# S7CAS-PLEIADES-CARTE-MERE_P02_FPGA_B4B5.net
KiCad netlist of a schematic drawn in Altium Designer
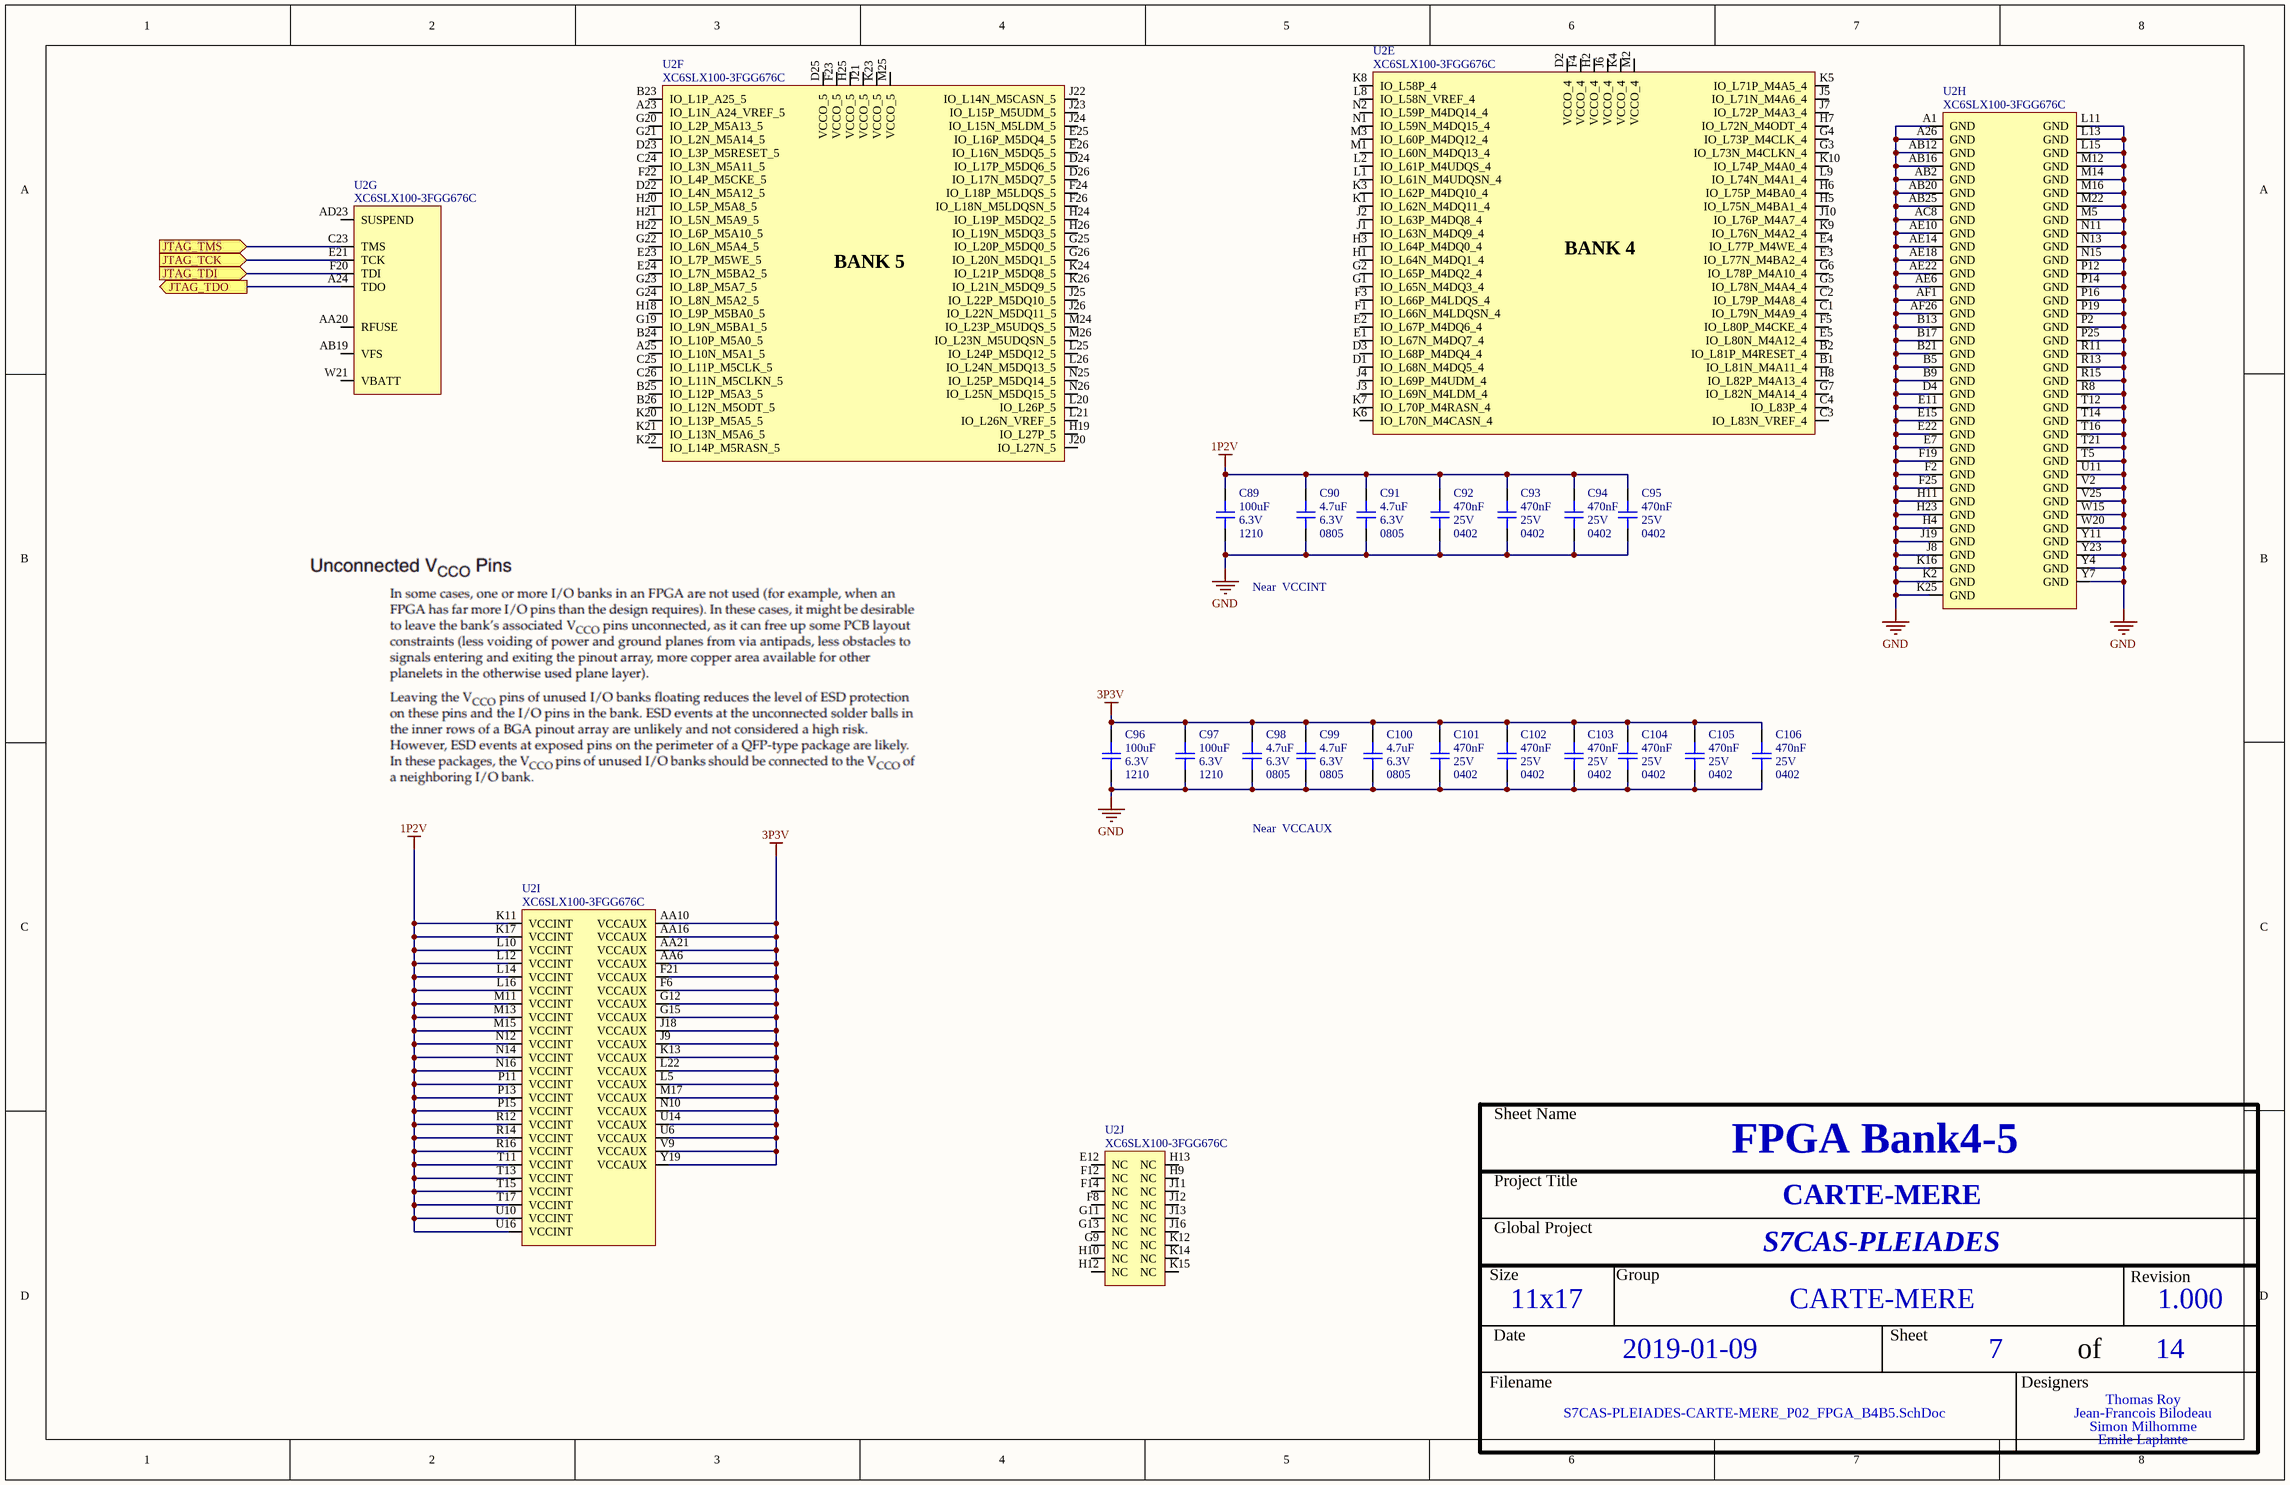
[diagram p0: S7CAS-PLEIADES-CARTE-MERE_P02_FPGA_B4B5.SchDoc]

(export (version "E")
  (design (tool "Eeschema 10.0.6"))
  (components
    (comp (ref "C89")
      (value "100uF")
      (footprint "CAP_1210")
      (description "CAP - 1210")
      (fields
        (field (name "VOLTAGE") "6.3V")
        (field (name "PACKAGE") "1210")
        (field (name "CREATEDBY") "Jonathan Bouchard")
      )
      (libsource (lib "S7CAS_Lib2019_REV1_00") (part "CAP - 1210"))
    )
    (comp (ref "C90")
      (value "4.7uF")
      (footprint "CAP_0805")
      (description "CAP - 0805")
      (fields
        (field (name "VOLTAGE") "6.3V")
        (field (name "PACKAGE") "0805")
        (field (name "CREATEDBY") "Jonathan Bouchard")
      )
      (libsource (lib "S7CAS_Lib2019_REV1_00") (part "CAP - 0805"))
    )
    (comp (ref "C91")
      (value "4.7uF")
      (footprint "CAP_0805")
      (description "CAP - 0805")
      (fields
        (field (name "VOLTAGE") "6.3V")
        (field (name "PACKAGE") "0805")
        (field (name "CREATEDBY") "Jonathan Bouchard")
      )
      (libsource (lib "S7CAS_Lib2019_REV1_00") (part "CAP - 0805"))
    )
    (comp (ref "C92")
      (value "470nF")
      (footprint "CAP_0402")
      (description "CAP - 0402")
      (fields
        (field (name "VOLTAGE") "25V")
        (field (name "PACKAGE") "0402")
        (field (name "CREATEDBY") "Jonathan Bouchard")
      )
      (libsource (lib "S7CAS_Lib2019_REV1_00") (part "CAP - 0402"))
    )
    (comp (ref "C93")
      (value "470nF")
      (footprint "CAP_0402")
      (description "CAP - 0402")
      (fields
        (field (name "VOLTAGE") "25V")
        (field (name "PACKAGE") "0402")
        (field (name "CREATEDBY") "Jonathan Bouchard")
      )
      (libsource (lib "S7CAS_Lib2019_REV1_00") (part "CAP - 0402"))
    )
    (comp (ref "C94")
      (value "470nF")
      (footprint "CAP_0402")
      (description "CAP - 0402")
      (fields
        (field (name "VOLTAGE") "25V")
        (field (name "PACKAGE") "0402")
        (field (name "CREATEDBY") "Jonathan Bouchard")
      )
      (libsource (lib "S7CAS_Lib2019_REV1_00") (part "CAP - 0402"))
    )
    (comp (ref "C95")
      (value "470nF")
      (footprint "CAP_0402")
      (description "CAP - 0402")
      (fields
        (field (name "VOLTAGE") "25V")
        (field (name "PACKAGE") "0402")
        (field (name "CREATEDBY") "Jonathan Bouchard")
      )
      (libsource (lib "S7CAS_Lib2019_REV1_00") (part "CAP - 0402"))
    )
    (comp (ref "C96")
      (value "100uF")
      (footprint "CAP_1210")
      (description "CAP - 1210")
      (fields
        (field (name "VOLTAGE") "6.3V")
        (field (name "PACKAGE") "1210")
        (field (name "CREATEDBY") "Jonathan Bouchard")
      )
      (libsource (lib "S7CAS_Lib2019_REV1_00") (part "CAP - 1210"))
    )
    (comp (ref "C97")
      (value "100uF")
      (footprint "CAP_1210")
      (description "CAP - 1210")
      (fields
        (field (name "VOLTAGE") "6.3V")
        (field (name "PACKAGE") "1210")
        (field (name "CREATEDBY") "Jonathan Bouchard")
      )
      (libsource (lib "S7CAS_Lib2019_REV1_00") (part "CAP - 1210"))
    )
    (comp (ref "C98")
      (value "4.7uF")
      (footprint "CAP_0805")
      (description "CAP - 0805")
      (fields
        (field (name "VOLTAGE") "6.3V")
        (field (name "PACKAGE") "0805")
        (field (name "CREATEDBY") "Jonathan Bouchard")
      )
      (libsource (lib "S7CAS_Lib2019_REV1_00") (part "CAP - 0805"))
    )
    (comp (ref "C99")
      (value "4.7uF")
      (footprint "CAP_0805")
      (description "CAP - 0805")
      (fields
        (field (name "VOLTAGE") "6.3V")
        (field (name "PACKAGE") "0805")
        (field (name "CREATEDBY") "Jonathan Bouchard")
      )
      (libsource (lib "S7CAS_Lib2019_REV1_00") (part "CAP - 0805"))
    )
    (comp (ref "C100")
      (value "4.7uF")
      (footprint "CAP_0805")
      (description "CAP - 0805")
      (fields
        (field (name "VOLTAGE") "6.3V")
        (field (name "PACKAGE") "0805")
        (field (name "CREATEDBY") "Jonathan Bouchard")
      )
      (libsource (lib "S7CAS_Lib2019_REV1_00") (part "CAP - 0805"))
    )
    (comp (ref "C101")
      (value "470nF")
      (footprint "CAP_0402")
      (description "CAP - 0402")
      (fields
        (field (name "VOLTAGE") "25V")
        (field (name "PACKAGE") "0402")
        (field (name "CREATEDBY") "Jonathan Bouchard")
      )
      (libsource (lib "S7CAS_Lib2019_REV1_00") (part "CAP - 0402"))
    )
    (comp (ref "C102")
      (value "470nF")
      (footprint "CAP_0402")
      (description "CAP - 0402")
      (fields
        (field (name "VOLTAGE") "25V")
        (field (name "PACKAGE") "0402")
        (field (name "CREATEDBY") "Jonathan Bouchard")
      )
      (libsource (lib "S7CAS_Lib2019_REV1_00") (part "CAP - 0402"))
    )
    (comp (ref "C103")
      (value "470nF")
      (footprint "CAP_0402")
      (description "CAP - 0402")
      (fields
        (field (name "VOLTAGE") "25V")
        (field (name "PACKAGE") "0402")
        (field (name "CREATEDBY") "Jonathan Bouchard")
      )
      (libsource (lib "S7CAS_Lib2019_REV1_00") (part "CAP - 0402"))
    )
    (comp (ref "C104")
      (value "470nF")
      (footprint "CAP_0402")
      (description "CAP - 0402")
      (fields
        (field (name "VOLTAGE") "25V")
        (field (name "PACKAGE") "0402")
        (field (name "CREATEDBY") "Jonathan Bouchard")
      )
      (libsource (lib "S7CAS_Lib2019_REV1_00") (part "CAP - 0402"))
    )
    (comp (ref "C105")
      (value "470nF")
      (footprint "CAP_0402")
      (description "CAP - 0402")
      (fields
        (field (name "VOLTAGE") "25V")
        (field (name "PACKAGE") "0402")
        (field (name "CREATEDBY") "Jonathan Bouchard")
      )
      (libsource (lib "S7CAS_Lib2019_REV1_00") (part "CAP - 0402"))
    )
    (comp (ref "C106")
      (value "470nF")
      (footprint "CAP_0402")
      (description "CAP - 0402")
      (fields
        (field (name "VOLTAGE") "25V")
        (field (name "PACKAGE") "0402")
        (field (name "CREATEDBY") "Jonathan Bouchard")
      )
      (libsource (lib "S7CAS_Lib2019_REV1_00") (part "CAP - 0402"))
    )
    (comp (ref "U2")
      (value "XC6SLX100-3FGG676C")
      (footprint "FPGA_XILINX_FGG676")
      (description "FPGA - XILINX SPARTAN 6 480 I/O - BGA-676")
      (fields
        (field (name "VOLTAGE") "1.14 V ~ 1.26 V")
        (field (name "MFG") "Xilinx")
        (field (name "CREATEDBY") "Jonathan Bouchard")
      )
      (libsource (lib "S7CAS_Lib2019_REV1_00") (part "FPGA_XC6SLX100-3FGG676C"))
    )
  )
  (nets
    (net (code "1") (name "/JTAG_TCK") (class "Default")
      (node (ref "U2") (pin "E21") (pinfunction "TCK_E21") (pintype "passive"))
    )
    (net (code "2") (name "/JTAG_TDI") (class "Default")
      (node (ref "U2") (pin "F20") (pinfunction "TDI_F20") (pintype "passive"))
    )
    (net (code "3") (name "/JTAG_TDO") (class "Default")
      (node (ref "U2") (pin "A24") (pinfunction "TDO_A24") (pintype "passive"))
    )
    (net (code "4") (name "/JTAG_TMS") (class "Default")
      (node (ref "U2") (pin "C23") (pinfunction "TMS_C23") (pintype "passive"))
    )
    (net (code "5") (name "1P2V") (class "Default")
      (node (ref "C89") (pin "2") (pinfunction "2_2") (pintype "passive"))
      (node (ref "C90") (pin "2") (pinfunction "2_2") (pintype "passive"))
      (node (ref "C91") (pin "2") (pinfunction "2_2") (pintype "passive"))
      (node (ref "C92") (pin "2") (pinfunction "2_2") (pintype "passive"))
      (node (ref "C93") (pin "2") (pinfunction "2_2") (pintype "passive"))
      (node (ref "C94") (pin "2") (pinfunction "2_2") (pintype "passive"))
      (node (ref "C95") (pin "2") (pinfunction "2_2") (pintype "passive"))
      (node (ref "U2") (pin "K11") (pinfunction "VCCINT_K11") (pintype "passive"))
      (node (ref "U2") (pin "K17") (pinfunction "VCCINT_K17") (pintype "passive"))
      (node (ref "U2") (pin "L10") (pinfunction "VCCINT_L10") (pintype "passive"))
      (node (ref "U2") (pin "L12") (pinfunction "VCCINT_L12") (pintype "passive"))
      (node (ref "U2") (pin "L14") (pinfunction "VCCINT_L14") (pintype "passive"))
      (node (ref "U2") (pin "L16") (pinfunction "VCCINT_L16") (pintype "passive"))
      (node (ref "U2") (pin "M11") (pinfunction "VCCINT_M11") (pintype "passive"))
      (node (ref "U2") (pin "M13") (pinfunction "VCCINT_M13") (pintype "passive"))
      (node (ref "U2") (pin "M15") (pinfunction "VCCINT_M15") (pintype "passive"))
      (node (ref "U2") (pin "N12") (pinfunction "VCCINT_N12") (pintype "passive"))
      (node (ref "U2") (pin "N14") (pinfunction "VCCINT_N14") (pintype "passive"))
      (node (ref "U2") (pin "N16") (pinfunction "VCCINT_N16") (pintype "passive"))
      (node (ref "U2") (pin "P11") (pinfunction "VCCINT_P11") (pintype "passive"))
      (node (ref "U2") (pin "P13") (pinfunction "VCCINT_P13") (pintype "passive"))
      (node (ref "U2") (pin "P15") (pinfunction "VCCINT_P15") (pintype "passive"))
      (node (ref "U2") (pin "R12") (pinfunction "VCCINT_R12") (pintype "passive"))
      (node (ref "U2") (pin "R14") (pinfunction "VCCINT_R14") (pintype "passive"))
      (node (ref "U2") (pin "R16") (pinfunction "VCCINT_R16") (pintype "passive"))
      (node (ref "U2") (pin "T11") (pinfunction "VCCINT_T11") (pintype "passive"))
      (node (ref "U2") (pin "T13") (pinfunction "VCCINT_T13") (pintype "passive"))
      (node (ref "U2") (pin "T15") (pinfunction "VCCINT_T15") (pintype "passive"))
      (node (ref "U2") (pin "T17") (pinfunction "VCCINT_T17") (pintype "passive"))
      (node (ref "U2") (pin "U10") (pinfunction "VCCINT_U10") (pintype "passive"))
      (node (ref "U2") (pin "U16") (pinfunction "VCCINT_U16") (pintype "passive"))
    )
    (net (code "6") (name "3P3V") (class "Default")
      (node (ref "C100") (pin "2") (pinfunction "2_2") (pintype "passive"))
      (node (ref "C101") (pin "2") (pinfunction "2_2") (pintype "passive"))
      (node (ref "C102") (pin "2") (pinfunction "2_2") (pintype "passive"))
      (node (ref "C103") (pin "2") (pinfunction "2_2") (pintype "passive"))
      (node (ref "C104") (pin "2") (pinfunction "2_2") (pintype "passive"))
      (node (ref "C105") (pin "2") (pinfunction "2_2") (pintype "passive"))
      (node (ref "C106") (pin "2") (pinfunction "2_2") (pintype "passive"))
      (node (ref "C96") (pin "2") (pinfunction "2_2") (pintype "passive"))
      (node (ref "C97") (pin "2") (pinfunction "2_2") (pintype "passive"))
      (node (ref "C98") (pin "2") (pinfunction "2_2") (pintype "passive"))
      (node (ref "C99") (pin "2") (pinfunction "2_2") (pintype "passive"))
      (node (ref "U2") (pin "AA10") (pinfunction "VCCAUX_AA10") (pintype "passive"))
      (node (ref "U2") (pin "AA16") (pinfunction "VCCAUX_AA16") (pintype "passive"))
      (node (ref "U2") (pin "AA21") (pinfunction "VCCAUX_AA21") (pintype "passive"))
      (node (ref "U2") (pin "AA6") (pinfunction "VCCAUX_AA6") (pintype "passive"))
      (node (ref "U2") (pin "F21") (pinfunction "VCCAUX_F21") (pintype "passive"))
      (node (ref "U2") (pin "F6") (pinfunction "VCCAUX_F6") (pintype "passive"))
      (node (ref "U2") (pin "G12") (pinfunction "VCCAUX_G12") (pintype "passive"))
      (node (ref "U2") (pin "G15") (pinfunction "VCCAUX_G15") (pintype "passive"))
      (node (ref "U2") (pin "J18") (pinfunction "VCCAUX_J18") (pintype "passive"))
      (node (ref "U2") (pin "J9") (pinfunction "VCCAUX_J9") (pintype "passive"))
      (node (ref "U2") (pin "K13") (pinfunction "VCCAUX_K13") (pintype "passive"))
      (node (ref "U2") (pin "L22") (pinfunction "VCCAUX_L22") (pintype "passive"))
      (node (ref "U2") (pin "L5") (pinfunction "VCCAUX_L5") (pintype "passive"))
      (node (ref "U2") (pin "M17") (pinfunction "VCCAUX_M17") (pintype "passive"))
      (node (ref "U2") (pin "N10") (pinfunction "VCCAUX_N10") (pintype "passive"))
      (node (ref "U2") (pin "U14") (pinfunction "VCCAUX_U14") (pintype "passive"))
      (node (ref "U2") (pin "U6") (pinfunction "VCCAUX_U6") (pintype "passive"))
      (node (ref "U2") (pin "V9") (pinfunction "VCCAUX_V9") (pintype "passive"))
      (node (ref "U2") (pin "Y19") (pinfunction "VCCAUX_Y19") (pintype "passive"))
    )
    (net (code "7") (name "GND") (class "Default")
      (node (ref "C100") (pin "1") (pinfunction "1_1") (pintype "passive"))
      (node (ref "C101") (pin "1") (pinfunction "1_1") (pintype "passive"))
      (node (ref "C102") (pin "1") (pinfunction "1_1") (pintype "passive"))
      (node (ref "C103") (pin "1") (pinfunction "1_1") (pintype "passive"))
      (node (ref "C104") (pin "1") (pinfunction "1_1") (pintype "passive"))
      (node (ref "C105") (pin "1") (pinfunction "1_1") (pintype "passive"))
      (node (ref "C106") (pin "1") (pinfunction "1_1") (pintype "passive"))
      (node (ref "C89") (pin "1") (pinfunction "1_1") (pintype "passive"))
      (node (ref "C90") (pin "1") (pinfunction "1_1") (pintype "passive"))
      (node (ref "C91") (pin "1") (pinfunction "1_1") (pintype "passive"))
      (node (ref "C92") (pin "1") (pinfunction "1_1") (pintype "passive"))
      (node (ref "C93") (pin "1") (pinfunction "1_1") (pintype "passive"))
      (node (ref "C94") (pin "1") (pinfunction "1_1") (pintype "passive"))
      (node (ref "C95") (pin "1") (pinfunction "1_1") (pintype "passive"))
      (node (ref "C96") (pin "1") (pinfunction "1_1") (pintype "passive"))
      (node (ref "C97") (pin "1") (pinfunction "1_1") (pintype "passive"))
      (node (ref "C98") (pin "1") (pinfunction "1_1") (pintype "passive"))
      (node (ref "C99") (pin "1") (pinfunction "1_1") (pintype "passive"))
      (node (ref "U2") (pin "A1") (pinfunction "GND_A1") (pintype "passive"))
      (node (ref "U2") (pin "A26") (pinfunction "GND_A26") (pintype "passive"))
      (node (ref "U2") (pin "AB12") (pinfunction "GND_AB12") (pintype "passive"))
      (node (ref "U2") (pin "AB16") (pinfunction "GND_AB16") (pintype "passive"))
      (node (ref "U2") (pin "AB2") (pinfunction "GND_AB2") (pintype "passive"))
      (node (ref "U2") (pin "AB20") (pinfunction "GND_AB20") (pintype "passive"))
      (node (ref "U2") (pin "AB25") (pinfunction "GND_AB25") (pintype "passive"))
      (node (ref "U2") (pin "AC8") (pinfunction "GND_AC8") (pintype "passive"))
      (node (ref "U2") (pin "AE10") (pinfunction "GND_AE10") (pintype "passive"))
      (node (ref "U2") (pin "AE14") (pinfunction "GND_AE14") (pintype "passive"))
      (node (ref "U2") (pin "AE18") (pinfunction "GND_AE18") (pintype "passive"))
      (node (ref "U2") (pin "AE22") (pinfunction "GND_AE22") (pintype "passive"))
      (node (ref "U2") (pin "AE6") (pinfunction "GND_AE6") (pintype "passive"))
      (node (ref "U2") (pin "AF1") (pinfunction "GND_AF1") (pintype "passive"))
      (node (ref "U2") (pin "AF26") (pinfunction "GND_AF26") (pintype "passive"))
      (node (ref "U2") (pin "B13") (pinfunction "GND_B13") (pintype "passive"))
      (node (ref "U2") (pin "B17") (pinfunction "GND_B17") (pintype "passive"))
      (node (ref "U2") (pin "B21") (pinfunction "GND_B21") (pintype "passive"))
      (node (ref "U2") (pin "B5") (pinfunction "GND_B5") (pintype "passive"))
      (node (ref "U2") (pin "B9") (pinfunction "GND_B9") (pintype "passive"))
      (node (ref "U2") (pin "D4") (pinfunction "GND_D4") (pintype "passive"))
      (node (ref "U2") (pin "E11") (pinfunction "GND_E11") (pintype "passive"))
      (node (ref "U2") (pin "E15") (pinfunction "GND_E15") (pintype "passive"))
      (node (ref "U2") (pin "E22") (pinfunction "GND_E22") (pintype "passive"))
      (node (ref "U2") (pin "E7") (pinfunction "GND_E7") (pintype "passive"))
      (node (ref "U2") (pin "F19") (pinfunction "GND_F19") (pintype "passive"))
      (node (ref "U2") (pin "F2") (pinfunction "GND_F2") (pintype "passive"))
      (node (ref "U2") (pin "F25") (pinfunction "GND_F25") (pintype "passive"))
      (node (ref "U2") (pin "H11") (pinfunction "GND_H11") (pintype "passive"))
      (node (ref "U2") (pin "H23") (pinfunction "GND_H23") (pintype "passive"))
      (node (ref "U2") (pin "H4") (pinfunction "GND_H4") (pintype "passive"))
      (node (ref "U2") (pin "J19") (pinfunction "GND_J19") (pintype "passive"))
      (node (ref "U2") (pin "J8") (pinfunction "GND_J8") (pintype "passive"))
      (node (ref "U2") (pin "K16") (pinfunction "GND_K16") (pintype "passive"))
      (node (ref "U2") (pin "K2") (pinfunction "GND_K2") (pintype "passive"))
      (node (ref "U2") (pin "K25") (pinfunction "GND_K25") (pintype "passive"))
      (node (ref "U2") (pin "L11") (pinfunction "GND_L11") (pintype "passive"))
      (node (ref "U2") (pin "L13") (pinfunction "GND_L13") (pintype "passive"))
      (node (ref "U2") (pin "L15") (pinfunction "GND_L15") (pintype "passive"))
      (node (ref "U2") (pin "M12") (pinfunction "GND_M12") (pintype "passive"))
      (node (ref "U2") (pin "M14") (pinfunction "GND_M14") (pintype "passive"))
      (node (ref "U2") (pin "M16") (pinfunction "GND_M16") (pintype "passive"))
      (node (ref "U2") (pin "M22") (pinfunction "GND_M22") (pintype "passive"))
      (node (ref "U2") (pin "M5") (pinfunction "GND_M5") (pintype "passive"))
      (node (ref "U2") (pin "N11") (pinfunction "GND_N11") (pintype "passive"))
      (node (ref "U2") (pin "N13") (pinfunction "GND_N13") (pintype "passive"))
      (node (ref "U2") (pin "N15") (pinfunction "GND_N15") (pintype "passive"))
      (node (ref "U2") (pin "P12") (pinfunction "GND_P12") (pintype "passive"))
      (node (ref "U2") (pin "P14") (pinfunction "GND_P14") (pintype "passive"))
      (node (ref "U2") (pin "P16") (pinfunction "GND_P16") (pintype "passive"))
      (node (ref "U2") (pin "P19") (pinfunction "GND_P19") (pintype "passive"))
      (node (ref "U2") (pin "P2") (pinfunction "GND_P2") (pintype "passive"))
      (node (ref "U2") (pin "P25") (pinfunction "GND_P25") (pintype "passive"))
      (node (ref "U2") (pin "R11") (pinfunction "GND_R11") (pintype "passive"))
      (node (ref "U2") (pin "R13") (pinfunction "GND_R13") (pintype "passive"))
      (node (ref "U2") (pin "R15") (pinfunction "GND_R15") (pintype "passive"))
      (node (ref "U2") (pin "R8") (pinfunction "GND_R8") (pintype "passive"))
      (node (ref "U2") (pin "T12") (pinfunction "GND_T12") (pintype "passive"))
      (node (ref "U2") (pin "T14") (pinfunction "GND_T14") (pintype "passive"))
      (node (ref "U2") (pin "T16") (pinfunction "GND_T16") (pintype "passive"))
      (node (ref "U2") (pin "T21") (pinfunction "GND_T21") (pintype "passive"))
      (node (ref "U2") (pin "T5") (pinfunction "GND_T5") (pintype "passive"))
      (node (ref "U2") (pin "U11") (pinfunction "GND_U11") (pintype "passive"))
      (node (ref "U2") (pin "V2") (pinfunction "GND_V2") (pintype "passive"))
      (node (ref "U2") (pin "V25") (pinfunction "GND_V25") (pintype "passive"))
      (node (ref "U2") (pin "W15") (pinfunction "GND_W15") (pintype "passive"))
      (node (ref "U2") (pin "W20") (pinfunction "GND_W20") (pintype "passive"))
      (node (ref "U2") (pin "Y11") (pinfunction "GND_Y11") (pintype "passive"))
      (node (ref "U2") (pin "Y23") (pinfunction "GND_Y23") (pintype "passive"))
      (node (ref "U2") (pin "Y4") (pinfunction "GND_Y4") (pintype "passive"))
      (node (ref "U2") (pin "Y7") (pinfunction "GND_Y7") (pintype "passive"))
    )
    (net (code "8") (name "unconnected-(U2E-IO_L58N_VREF_4-PadL8)") (class "Default")
      (node (ref "U2") (pin "L8") (pinfunction "IO_L58N_VREF_4_L8") (pintype "passive"))
    )
    (net (code "9") (name "unconnected-(U2E-IO_L58P_4-PadK8)") (class "Default")
      (node (ref "U2") (pin "K8") (pinfunction "IO_L58P_4_K8") (pintype "passive"))
    )
    (net (code "10") (name "unconnected-(U2E-IO_L59N_M4DQ15_4-PadN1)") (class "Default")
      (node (ref "U2") (pin "N1") (pinfunction "IO_L59N_M4DQ15_4_N1") (pintype "passive"))
    )
    (net (code "11") (name "unconnected-(U2E-IO_L59P_M4DQ14_4-PadN2)") (class "Default")
      (node (ref "U2") (pin "N2") (pinfunction "IO_L59P_M4DQ14_4_N2") (pintype "passive"))
    )
    (net (code "12") (name "unconnected-(U2E-IO_L60N_M4DQ13_4-PadM1)") (class "Default")
      (node (ref "U2") (pin "M1") (pinfunction "IO_L60N_M4DQ13_4_M1") (pintype "passive"))
    )
    (net (code "13") (name "unconnected-(U2E-IO_L60P_M4DQ12_4-PadM3)") (class "Default")
      (node (ref "U2") (pin "M3") (pinfunction "IO_L60P_M4DQ12_4_M3") (pintype "passive"))
    )
    (net (code "14") (name "unconnected-(U2E-IO_L61N_M4UDQSN_4-PadL1)") (class "Default")
      (node (ref "U2") (pin "L1") (pinfunction "IO_L61N_M4UDQSN_4_L1") (pintype "passive"))
    )
    (net (code "15") (name "unconnected-(U2E-IO_L61P_M4UDQS_4-PadL2)") (class "Default")
      (node (ref "U2") (pin "L2") (pinfunction "IO_L61P_M4UDQS_4_L2") (pintype "passive"))
    )
    (net (code "16") (name "unconnected-(U2E-IO_L62N_M4DQ11_4-PadK1)") (class "Default")
      (node (ref "U2") (pin "K1") (pinfunction "IO_L62N_M4DQ11_4_K1") (pintype "passive"))
    )
    (net (code "17") (name "unconnected-(U2E-IO_L62P_M4DQ10_4-PadK3)") (class "Default")
      (node (ref "U2") (pin "K3") (pinfunction "IO_L62P_M4DQ10_4_K3") (pintype "passive"))
    )
    (net (code "18") (name "unconnected-(U2E-IO_L63N_M4DQ9_4-PadJ1)") (class "Default")
      (node (ref "U2") (pin "J1") (pinfunction "IO_L63N_M4DQ9_4_J1") (pintype "passive"))
    )
    (net (code "19") (name "unconnected-(U2E-IO_L63P_M4DQ8_4-PadJ2)") (class "Default")
      (node (ref "U2") (pin "J2") (pinfunction "IO_L63P_M4DQ8_4_J2") (pintype "passive"))
    )
    (net (code "20") (name "unconnected-(U2E-IO_L64N_M4DQ1_4-PadH1)") (class "Default")
      (node (ref "U2") (pin "H1") (pinfunction "IO_L64N_M4DQ1_4_H1") (pintype "passive"))
    )
    (net (code "21") (name "unconnected-(U2E-IO_L64P_M4DQ0_4-PadH3)") (class "Default")
      (node (ref "U2") (pin "H3") (pinfunction "IO_L64P_M4DQ0_4_H3") (pintype "passive"))
    )
    (net (code "22") (name "unconnected-(U2E-IO_L65N_M4DQ3_4-PadG1)") (class "Default")
      (node (ref "U2") (pin "G1") (pinfunction "IO_L65N_M4DQ3_4_G1") (pintype "passive"))
    )
    (net (code "23") (name "unconnected-(U2E-IO_L65P_M4DQ2_4-PadG2)") (class "Default")
      (node (ref "U2") (pin "G2") (pinfunction "IO_L65P_M4DQ2_4_G2") (pintype "passive"))
    )
    (net (code "24") (name "unconnected-(U2E-IO_L66N_M4LDQSN_4-PadF1)") (class "Default")
      (node (ref "U2") (pin "F1") (pinfunction "IO_L66N_M4LDQSN_4_F1") (pintype "passive"))
    )
    (net (code "25") (name "unconnected-(U2E-IO_L66P_M4LDQS_4-PadF3)") (class "Default")
      (node (ref "U2") (pin "F3") (pinfunction "IO_L66P_M4LDQS_4_F3") (pintype "passive"))
    )
    (net (code "26") (name "unconnected-(U2E-IO_L67N_M4DQ7_4-PadE1)") (class "Default")
      (node (ref "U2") (pin "E1") (pinfunction "IO_L67N_M4DQ7_4_E1") (pintype "passive"))
    )
    (net (code "27") (name "unconnected-(U2E-IO_L67P_M4DQ6_4-PadE2)") (class "Default")
      (node (ref "U2") (pin "E2") (pinfunction "IO_L67P_M4DQ6_4_E2") (pintype "passive"))
    )
    (net (code "28") (name "unconnected-(U2E-IO_L68N_M4DQ5_4-PadD1)") (class "Default")
      (node (ref "U2") (pin "D1") (pinfunction "IO_L68N_M4DQ5_4_D1") (pintype "passive"))
    )
    (net (code "29") (name "unconnected-(U2E-IO_L68P_M4DQ4_4-PadD3)") (class "Default")
      (node (ref "U2") (pin "D3") (pinfunction "IO_L68P_M4DQ4_4_D3") (pintype "passive"))
    )
    (net (code "30") (name "unconnected-(U2E-IO_L69N_M4LDM_4-PadJ3)") (class "Default")
      (node (ref "U2") (pin "J3") (pinfunction "IO_L69N_M4LDM_4_J3") (pintype "passive"))
    )
    (net (code "31") (name "unconnected-(U2E-IO_L69P_M4UDM_4-PadJ4)") (class "Default")
      (node (ref "U2") (pin "J4") (pinfunction "IO_L69P_M4UDM_4_J4") (pintype "passive"))
    )
    (net (code "32") (name "unconnected-(U2E-IO_L70N_M4CASN_4-PadK6)") (class "Default")
      (node (ref "U2") (pin "K6") (pinfunction "IO_L70N_M4CASN_4_K6") (pintype "passive"))
    )
    (net (code "33") (name "unconnected-(U2E-IO_L70P_M4RASN_4-PadK7)") (class "Default")
      (node (ref "U2") (pin "K7") (pinfunction "IO_L70P_M4RASN_4_K7") (pintype "passive"))
    )
    (net (code "34") (name "unconnected-(U2E-IO_L71N_M4A6_4-PadJ5)") (class "Default")
      (node (ref "U2") (pin "J5") (pinfunction "IO_L71N_M4A6_4_J5") (pintype "passive"))
    )
    (net (code "35") (name "unconnected-(U2E-IO_L71P_M4A5_4-PadK5)") (class "Default")
      (node (ref "U2") (pin "K5") (pinfunction "IO_L71P_M4A5_4_K5") (pintype "passive"))
    )
    (net (code "36") (name "unconnected-(U2E-IO_L72N_M4ODT_4-PadH7)") (class "Default")
      (node (ref "U2") (pin "H7") (pinfunction "IO_L72N_M4ODT_4_H7") (pintype "passive"))
    )
    (net (code "37") (name "unconnected-(U2E-IO_L72P_M4A3_4-PadJ7)") (class "Default")
      (node (ref "U2") (pin "J7") (pinfunction "IO_L72P_M4A3_4_J7") (pintype "passive"))
    )
    (net (code "38") (name "unconnected-(U2E-IO_L73N_M4CLKN_4-PadG3)") (class "Default")
      (node (ref "U2") (pin "G3") (pinfunction "IO_L73N_M4CLKN_4_G3") (pintype "passive"))
    )
    (net (code "39") (name "unconnected-(U2E-IO_L73P_M4CLK_4-PadG4)") (class "Default")
      (node (ref "U2") (pin "G4") (pinfunction "IO_L73P_M4CLK_4_G4") (pintype "passive"))
    )
    (net (code "40") (name "unconnected-(U2E-IO_L74N_M4A1_4-PadL9)") (class "Default")
      (node (ref "U2") (pin "L9") (pinfunction "IO_L74N_M4A1_4_L9") (pintype "passive"))
    )
    (net (code "41") (name "unconnected-(U2E-IO_L74P_M4A0_4-PadK10)") (class "Default")
      (node (ref "U2") (pin "K10") (pinfunction "IO_L74P_M4A0_4_K10") (pintype "passive"))
    )
    (net (code "42") (name "unconnected-(U2E-IO_L75N_M4BA1_4-PadH5)") (class "Default")
      (node (ref "U2") (pin "H5") (pinfunction "IO_L75N_M4BA1_4_H5") (pintype "passive"))
    )
    (net (code "43") (name "unconnected-(U2E-IO_L75P_M4BA0_4-PadH6)") (class "Default")
      (node (ref "U2") (pin "H6") (pinfunction "IO_L75P_M4BA0_4_H6") (pintype "passive"))
    )
    (net (code "44") (name "unconnected-(U2E-IO_L76N_M4A2_4-PadK9)") (class "Default")
      (node (ref "U2") (pin "K9") (pinfunction "IO_L76N_M4A2_4_K9") (pintype "passive"))
    )
    (net (code "45") (name "unconnected-(U2E-IO_L76P_M4A7_4-PadJ10)") (class "Default")
      (node (ref "U2") (pin "J10") (pinfunction "IO_L76P_M4A7_4_J10") (pintype "passive"))
    )
    (net (code "46") (name "unconnected-(U2E-IO_L77N_M4BA2_4-PadE3)") (class "Default")
      (node (ref "U2") (pin "E3") (pinfunction "IO_L77N_M4BA2_4_E3") (pintype "passive"))
    )
    (net (code "47") (name "unconnected-(U2E-IO_L77P_M4WE_4-PadE4)") (class "Default")
      (node (ref "U2") (pin "E4") (pinfunction "IO_L77P_M4WE_4_E4") (pintype "passive"))
    )
    (net (code "48") (name "unconnected-(U2E-IO_L78N_M4A4_4-PadG5)") (class "Default")
      (node (ref "U2") (pin "G5") (pinfunction "IO_L78N_M4A4_4_G5") (pintype "passive"))
    )
    (net (code "49") (name "unconnected-(U2E-IO_L78P_M4A10_4-PadG6)") (class "Default")
      (node (ref "U2") (pin "G6") (pinfunction "IO_L78P_M4A10_4_G6") (pintype "passive"))
    )
    (net (code "50") (name "unconnected-(U2E-IO_L79N_M4A9_4-PadC1)") (class "Default")
      (node (ref "U2") (pin "C1") (pinfunction "IO_L79N_M4A9_4_C1") (pintype "passive"))
    )
    (net (code "51") (name "unconnected-(U2E-IO_L79P_M4A8_4-PadC2)") (class "Default")
      (node (ref "U2") (pin "C2") (pinfunction "IO_L79P_M4A8_4_C2") (pintype "passive"))
    )
    (net (code "52") (name "unconnected-(U2E-IO_L80N_M4A12_4-PadE5)") (class "Default")
      (node (ref "U2") (pin "E5") (pinfunction "IO_L80N_M4A12_4_E5") (pintype "passive"))
    )
    (net (code "53") (name "unconnected-(U2E-IO_L80P_M4CKE_4-PadF5)") (class "Default")
      (node (ref "U2") (pin "F5") (pinfunction "IO_L80P_M4CKE_4_F5") (pintype "passive"))
    )
    (net (code "54") (name "unconnected-(U2E-IO_L81N_M4A11_4-PadB1)") (class "Default")
      (node (ref "U2") (pin "B1") (pinfunction "IO_L81N_M4A11_4_B1") (pintype "passive"))
    )
    (net (code "55") (name "unconnected-(U2E-IO_L81P_M4RESET_4-PadB2)") (class "Default")
      (node (ref "U2") (pin "B2") (pinfunction "IO_L81P_M4RESET_4_B2") (pintype "passive"))
    )
    (net (code "56") (name "unconnected-(U2E-IO_L82N_M4A14_4-PadG7)") (class "Default")
      (node (ref "U2") (pin "G7") (pinfunction "IO_L82N_M4A14_4_G7") (pintype "passive"))
    )
    (net (code "57") (name "unconnected-(U2E-IO_L82P_M4A13_4-PadH8)") (class "Default")
      (node (ref "U2") (pin "H8") (pinfunction "IO_L82P_M4A13_4_H8") (pintype "passive"))
    )
    (net (code "58") (name "unconnected-(U2E-IO_L83N_VREF_4-PadC3)") (class "Default")
      (node (ref "U2") (pin "C3") (pinfunction "IO_L83N_VREF_4_C3") (pintype "passive"))
    )
    (net (code "59") (name "unconnected-(U2E-IO_L83P_4-PadC4)") (class "Default")
      (node (ref "U2") (pin "C4") (pinfunction "IO_L83P_4_C4") (pintype "passive"))
    )
    (net (code "60") (name "unconnected-(U2E-VCCO_4-PadD2)") (class "Default")
      (node (ref "U2") (pin "D2") (pinfunction "VCCO_4_D2") (pintype "passive"))
    )
    (net (code "61") (name "unconnected-(U2E-VCCO_4-PadF4)") (class "Default")
      (node (ref "U2") (pin "F4") (pinfunction "VCCO_4_F4") (pintype "passive"))
    )
    (net (code "62") (name "unconnected-(U2E-VCCO_4-PadH2)") (class "Default")
      (node (ref "U2") (pin "H2") (pinfunction "VCCO_4_H2") (pintype "passive"))
    )
    (net (code "63") (name "unconnected-(U2E-VCCO_4-PadJ6)") (class "Default")
      (node (ref "U2") (pin "J6") (pinfunction "VCCO_4_J6") (pintype "passive"))
    )
    (net (code "64") (name "unconnected-(U2E-VCCO_4-PadK4)") (class "Default")
      (node (ref "U2") (pin "K4") (pinfunction "VCCO_4_K4") (pintype "passive"))
    )
    (net (code "65") (name "unconnected-(U2E-VCCO_4-PadM2)") (class "Default")
      (node (ref "U2") (pin "M2") (pinfunction "VCCO_4_M2") (pintype "passive"))
    )
    (net (code "66") (name "unconnected-(U2F-IO_L1N_A24_VREF_5-PadA23)") (class "Default")
      (node (ref "U2") (pin "A23") (pinfunction "IO_L1N_A24_VREF_5_A23") (pintype "passive"))
    )
    (net (code "67") (name "unconnected-(U2F-IO_L1P_A25_5-PadB23)") (class "Default")
      (node (ref "U2") (pin "B23") (pinfunction "IO_L1P_A25_5_B23") (pintype "passive"))
    )
    (net (code "68") (name "unconnected-(U2F-IO_L2N_M5A14_5-PadG21)") (class "Default")
      (node (ref "U2") (pin "G21") (pinfunction "IO_L2N_M5A14_5_G21") (pintype "passive"))
    )
    (net (code "69") (name "unconnected-(U2F-IO_L2P_M5A13_5-PadG20)") (class "Default")
      (node (ref "U2") (pin "G20") (pinfunction "IO_L2P_M5A13_5_G20") (pintype "passive"))
    )
    (net (code "70") (name "unconnected-(U2F-IO_L3N_M5A11_5-PadC24)") (class "Default")
      (node (ref "U2") (pin "C24") (pinfunction "IO_L3N_M5A11_5_C24") (pintype "passive"))
    )
    (net (code "71") (name "unconnected-(U2F-IO_L3P_M5RESET_5-PadD23)") (class "Default")
      (node (ref "U2") (pin "D23") (pinfunction "IO_L3P_M5RESET_5_D23") (pintype "passive"))
    )
    (net (code "72") (name "unconnected-(U2F-IO_L4N_M5A12_5-PadD22)") (class "Default")
      (node (ref "U2") (pin "D22") (pinfunction "IO_L4N_M5A12_5_D22") (pintype "passive"))
    )
    (net (code "73") (name "unconnected-(U2F-IO_L4P_M5CKE_5-PadF22)") (class "Default")
      (node (ref "U2") (pin "F22") (pinfunction "IO_L4P_M5CKE_5_F22") (pintype "passive"))
    )
    (net (code "74") (name "unconnected-(U2F-IO_L5N_M5A9_5-PadH21)") (class "Default")
      (node (ref "U2") (pin "H21") (pinfunction "IO_L5N_M5A9_5_H21") (pintype "passive"))
    )
    (net (code "75") (name "unconnected-(U2F-IO_L5P_M5A8_5-PadH20)") (class "Default")
      (node (ref "U2") (pin "H20") (pinfunction "IO_L5P_M5A8_5_H20") (pintype "passive"))
    )
    (net (code "76") (name "unconnected-(U2F-IO_L6N_M5A4_5-PadG22)") (class "Default")
      (node (ref "U2") (pin "G22") (pinfunction "IO_L6N_M5A4_5_G22") (pintype "passive"))
    )
    (net (code "77") (name "unconnected-(U2F-IO_L6P_M5A10_5-PadH22)") (class "Default")
      (node (ref "U2") (pin "H22") (pinfunction "IO_L6P_M5A10_5_H22") (pintype "passive"))
    )
    (net (code "78") (name "unconnected-(U2F-IO_L7N_M5BA2_5-PadE24)") (class "Default")
      (node (ref "U2") (pin "E24") (pinfunction "IO_L7N_M5BA2_5_E24") (pintype "passive"))
    )
    (net (code "79") (name "unconnected-(U2F-IO_L7P_M5WE_5-PadE23)") (class "Default")
      (node (ref "U2") (pin "E23") (pinfunction "IO_L7P_M5WE_5_E23") (pintype "passive"))
    )
    (net (code "80") (name "unconnected-(U2F-IO_L8N_M5A2_5-PadG24)") (class "Default")
      (node (ref "U2") (pin "G24") (pinfunction "IO_L8N_M5A2_5_G24") (pintype "passive"))
    )
    (net (code "81") (name "unconnected-(U2F-IO_L8P_M5A7_5-PadG23)") (class "Default")
      (node (ref "U2") (pin "G23") (pinfunction "IO_L8P_M5A7_5_G23") (pintype "passive"))
    )
    (net (code "82") (name "unconnected-(U2F-IO_L9N_M5BA1_5-PadG19)") (class "Default")
      (node (ref "U2") (pin "G19") (pinfunction "IO_L9N_M5BA1_5_G19") (pintype "passive"))
    )
    (net (code "83") (name "unconnected-(U2F-IO_L9P_M5BA0_5-PadH18)") (class "Default")
      (node (ref "U2") (pin "H18") (pinfunction "IO_L9P_M5BA0_5_H18") (pintype "passive"))
    )
    (net (code "84") (name "unconnected-(U2F-IO_L10N_M5A1_5-PadA25)") (class "Default")
      (node (ref "U2") (pin "A25") (pinfunction "IO_L10N_M5A1_5_A25") (pintype "passive"))
    )
    (net (code "85") (name "unconnected-(U2F-IO_L10P_M5A0_5-PadB24)") (class "Default")
      (node (ref "U2") (pin "B24") (pinfunction "IO_L10P_M5A0_5_B24") (pintype "passive"))
    )
    (net (code "86") (name "unconnected-(U2F-IO_L11N_M5CLKN_5-PadC26)") (class "Default")
      (node (ref "U2") (pin "C26") (pinfunction "IO_L11N_M5CLKN_5_C26") (pintype "passive"))
    )
    (net (code "87") (name "unconnected-(U2F-IO_L11P_M5CLK_5-PadC25)") (class "Default")
      (node (ref "U2") (pin "C25") (pinfunction "IO_L11P_M5CLK_5_C25") (pintype "passive"))
    )
    (net (code "88") (name "unconnected-(U2F-IO_L12N_M5ODT_5-PadB26)") (class "Default")
      (node (ref "U2") (pin "B26") (pinfunction "IO_L12N_M5ODT_5_B26") (pintype "passive"))
    )
    (net (code "89") (name "unconnected-(U2F-IO_L12P_M5A3_5-PadB25)") (class "Default")
      (node (ref "U2") (pin "B25") (pinfunction "IO_L12P_M5A3_5_B25") (pintype "passive"))
    )
    (net (code "90") (name "unconnected-(U2F-IO_L13N_M5A6_5-PadK21)") (class "Default")
      (node (ref "U2") (pin "K21") (pinfunction "IO_L13N_M5A6_5_K21") (pintype "passive"))
    )
    (net (code "91") (name "unconnected-(U2F-IO_L13P_M5A5_5-PadK20)") (class "Default")
      (node (ref "U2") (pin "K20") (pinfunction "IO_L13P_M5A5_5_K20") (pintype "passive"))
    )
    (net (code "92") (name "unconnected-(U2F-IO_L14N_M5CASN_5-PadJ22)") (class "Default")
      (node (ref "U2") (pin "J22") (pinfunction "IO_L14N_M5CASN_5_J22") (pintype "passive"))
    )
    (net (code "93") (name "unconnected-(U2F-IO_L14P_M5RASN_5-PadK22)") (class "Default")
      (node (ref "U2") (pin "K22") (pinfunction "IO_L14P_M5RASN_5_K22") (pintype "passive"))
    )
    (net (code "94") (name "unconnected-(U2F-IO_L15N_M5LDM_5-PadJ24)") (class "Default")
      (node (ref "U2") (pin "J24") (pinfunction "IO_L15N_M5LDM_5_J24") (pintype "passive"))
    )
    (net (code "95") (name "unconnected-(U2F-IO_L15P_M5UDM_5-PadJ23)") (class "Default")
      (node (ref "U2") (pin "J23") (pinfunction "IO_L15P_M5UDM_5_J23") (pintype "passive"))
    )
    (net (code "96") (name "unconnected-(U2F-IO_L16N_M5DQ5_5-PadE26)") (class "Default")
      (node (ref "U2") (pin "E26") (pinfunction "IO_L16N_M5DQ5_5_E26") (pintype "passive"))
    )
    (net (code "97") (name "unconnected-(U2F-IO_L16P_M5DQ4_5-PadE25)") (class "Default")
      (node (ref "U2") (pin "E25") (pinfunction "IO_L16P_M5DQ4_5_E25") (pintype "passive"))
    )
    (net (code "98") (name "unconnected-(U2F-IO_L17N_M5DQ7_5-PadD26)") (class "Default")
      (node (ref "U2") (pin "D26") (pinfunction "IO_L17N_M5DQ7_5_D26") (pintype "passive"))
    )
    (net (code "99") (name "unconnected-(U2F-IO_L17P_M5DQ6_5-PadD24)") (class "Default")
      (node (ref "U2") (pin "D24") (pinfunction "IO_L17P_M5DQ6_5_D24") (pintype "passive"))
    )
    (net (code "100") (name "unconnected-(U2F-IO_L18N_M5LDQSN_5-PadF26)") (class "Default")
      (node (ref "U2") (pin "F26") (pinfunction "IO_L18N_M5LDQSN_5_F26") (pintype "passive"))
    )
    (net (code "101") (name "unconnected-(U2F-IO_L18P_M5LDQS_5-PadF24)") (class "Default")
      (node (ref "U2") (pin "F24") (pinfunction "IO_L18P_M5LDQS_5_F24") (pintype "passive"))
    )
    (net (code "102") (name "unconnected-(U2F-IO_L19N_M5DQ3_5-PadH26)") (class "Default")
      (node (ref "U2") (pin "H26") (pinfunction "IO_L19N_M5DQ3_5_H26") (pintype "passive"))
    )
    (net (code "103") (name "unconnected-(U2F-IO_L19P_M5DQ2_5-PadH24)") (class "Default")
      (node (ref "U2") (pin "H24") (pinfunction "IO_L19P_M5DQ2_5_H24") (pintype "passive"))
    )
    (net (code "104") (name "unconnected-(U2F-IO_L20N_M5DQ1_5-PadG26)") (class "Default")
      (node (ref "U2") (pin "G26") (pinfunction "IO_L20N_M5DQ1_5_G26") (pintype "passive"))
    )
    (net (code "105") (name "unconnected-(U2F-IO_L20P_M5DQ0_5-PadG25)") (class "Default")
      (node (ref "U2") (pin "G25") (pinfunction "IO_L20P_M5DQ0_5_G25") (pintype "passive"))
    )
    (net (code "106") (name "unconnected-(U2F-IO_L21N_M5DQ9_5-PadK26)") (class "Default")
      (node (ref "U2") (pin "K26") (pinfunction "IO_L21N_M5DQ9_5_K26") (pintype "passive"))
    )
    (net (code "107") (name "unconnected-(U2F-IO_L21P_M5DQ8_5-PadK24)") (class "Default")
      (node (ref "U2") (pin "K24") (pinfunction "IO_L21P_M5DQ8_5_K24") (pintype "passive"))
    )
    (net (code "108") (name "unconnected-(U2F-IO_L22N_M5DQ11_5-PadJ26)") (class "Default")
      (node (ref "U2") (pin "J26") (pinfunction "IO_L22N_M5DQ11_5_J26") (pintype "passive"))
    )
    (net (code "109") (name "unconnected-(U2F-IO_L22P_M5DQ10_5-PadJ25)") (class "Default")
      (node (ref "U2") (pin "J25") (pinfunction "IO_L22P_M5DQ10_5_J25") (pintype "passive"))
    )
    (net (code "110") (name "unconnected-(U2F-IO_L23N_M5UDQSN_5-PadM26)") (class "Default")
      (node (ref "U2") (pin "M26") (pinfunction "IO_L23N_M5UDQSN_5_M26") (pintype "passive"))
    )
    (net (code "111") (name "unconnected-(U2F-IO_L23P_M5UDQS_5-PadM24)") (class "Default")
      (node (ref "U2") (pin "M24") (pinfunction "IO_L23P_M5UDQS_5_M24") (pintype "passive"))
    )
    (net (code "112") (name "unconnected-(U2F-IO_L24N_M5DQ13_5-PadL26)") (class "Default")
      (node (ref "U2") (pin "L26") (pinfunction "IO_L24N_M5DQ13_5_L26") (pintype "passive"))
    )
    (net (code "113") (name "unconnected-(U2F-IO_L24P_M5DQ12_5-PadL25)") (class "Default")
      (node (ref "U2") (pin "L25") (pinfunction "IO_L24P_M5DQ12_5_L25") (pintype "passive"))
    )
    (net (code "114") (name "unconnected-(U2F-IO_L25N_M5DQ15_5-PadN26)") (class "Default")
      (node (ref "U2") (pin "N26") (pinfunction "IO_L25N_M5DQ15_5_N26") (pintype "passive"))
    )
    (net (code "115") (name "unconnected-(U2F-IO_L25P_M5DQ14_5-PadN25)") (class "Default")
      (node (ref "U2") (pin "N25") (pinfunction "IO_L25P_M5DQ14_5_N25") (pintype "passive"))
    )
    (net (code "116") (name "unconnected-(U2F-IO_L26N_VREF_5-PadL21)") (class "Default")
      (node (ref "U2") (pin "L21") (pinfunction "IO_L26N_VREF_5_L21") (pintype "passive"))
    )
    (net (code "117") (name "unconnected-(U2F-IO_L26P_5-PadL20)") (class "Default")
      (node (ref "U2") (pin "L20") (pinfunction "IO_L26P_5_L20") (pintype "passive"))
    )
    (net (code "118") (name "unconnected-(U2F-IO_L27N_5-PadJ20)") (class "Default")
      (node (ref "U2") (pin "J20") (pinfunction "IO_L27N_5_J20") (pintype "passive"))
    )
    (net (code "119") (name "unconnected-(U2F-IO_L27P_5-PadH19)") (class "Default")
      (node (ref "U2") (pin "H19") (pinfunction "IO_L27P_5_H19") (pintype "passive"))
    )
    (net (code "120") (name "unconnected-(U2F-VCCO_5-PadD25)") (class "Default")
      (node (ref "U2") (pin "D25") (pinfunction "VCCO_5_D25") (pintype "passive"))
    )
    (net (code "121") (name "unconnected-(U2F-VCCO_5-PadF23)") (class "Default")
      (node (ref "U2") (pin "F23") (pinfunction "VCCO_5_F23") (pintype "passive"))
    )
    (net (code "122") (name "unconnected-(U2F-VCCO_5-PadH25)") (class "Default")
      (node (ref "U2") (pin "H25") (pinfunction "VCCO_5_H25") (pintype "passive"))
    )
    (net (code "123") (name "unconnected-(U2F-VCCO_5-PadJ21)") (class "Default")
      (node (ref "U2") (pin "J21") (pinfunction "VCCO_5_J21") (pintype "passive"))
    )
    (net (code "124") (name "unconnected-(U2F-VCCO_5-PadK23)") (class "Default")
      (node (ref "U2") (pin "K23") (pinfunction "VCCO_5_K23") (pintype "passive"))
    )
    (net (code "125") (name "unconnected-(U2F-VCCO_5-PadM25)") (class "Default")
      (node (ref "U2") (pin "M25") (pinfunction "VCCO_5_M25") (pintype "passive"))
    )
    (net (code "126") (name "unconnected-(U2G-RFUSE-PadAA20)") (class "Default")
      (node (ref "U2") (pin "AA20") (pinfunction "RFUSE_AA20") (pintype "passive"))
    )
    (net (code "127") (name "unconnected-(U2G-SUSPEND-PadAD23)") (class "Default")
      (node (ref "U2") (pin "AD23") (pinfunction "SUSPEND_AD23") (pintype "passive"))
    )
    (net (code "128") (name "unconnected-(U2G-VBATT-PadW21)") (class "Default")
      (node (ref "U2") (pin "W21") (pinfunction "VBATT_W21") (pintype "passive"))
    )
    (net (code "129") (name "unconnected-(U2G-VFS-PadAB19)") (class "Default")
      (node (ref "U2") (pin "AB19") (pinfunction "VFS_AB19") (pintype "passive"))
    )
    (net (code "130") (name "unconnected-(U2J-NC-PadE12)") (class "Default")
      (node (ref "U2") (pin "E12") (pinfunction "NC_E12") (pintype "passive"))
    )
    (net (code "131") (name "unconnected-(U2J-NC-PadF8)") (class "Default")
      (node (ref "U2") (pin "F8") (pinfunction "NC_F8") (pintype "passive"))
    )
    (net (code "132") (name "unconnected-(U2J-NC-PadF12)") (class "Default")
      (node (ref "U2") (pin "F12") (pinfunction "NC_F12") (pintype "passive"))
    )
    (net (code "133") (name "unconnected-(U2J-NC-PadF14)") (class "Default")
      (node (ref "U2") (pin "F14") (pinfunction "NC_F14") (pintype "passive"))
    )
    (net (code "134") (name "unconnected-(U2J-NC-PadG9)") (class "Default")
      (node (ref "U2") (pin "G9") (pinfunction "NC_G9") (pintype "passive"))
    )
    (net (code "135") (name "unconnected-(U2J-NC-PadG11)") (class "Default")
      (node (ref "U2") (pin "G11") (pinfunction "NC_G11") (pintype "passive"))
    )
    (net (code "136") (name "unconnected-(U2J-NC-PadG13)") (class "Default")
      (node (ref "U2") (pin "G13") (pinfunction "NC_G13") (pintype "passive"))
    )
    (net (code "137") (name "unconnected-(U2J-NC-PadH9)") (class "Default")
      (node (ref "U2") (pin "H9") (pinfunction "NC_H9") (pintype "passive"))
    )
    (net (code "138") (name "unconnected-(U2J-NC-PadH10)") (class "Default")
      (node (ref "U2") (pin "H10") (pinfunction "NC_H10") (pintype "passive"))
    )
    (net (code "139") (name "unconnected-(U2J-NC-PadH12)") (class "Default")
      (node (ref "U2") (pin "H12") (pinfunction "NC_H12") (pintype "passive"))
    )
    (net (code "140") (name "unconnected-(U2J-NC-PadH13)") (class "Default")
      (node (ref "U2") (pin "H13") (pinfunction "NC_H13") (pintype "passive"))
    )
    (net (code "141") (name "unconnected-(U2J-NC-PadJ11)") (class "Default")
      (node (ref "U2") (pin "J11") (pinfunction "NC_J11") (pintype "passive"))
    )
    (net (code "142") (name "unconnected-(U2J-NC-PadJ12)") (class "Default")
      (node (ref "U2") (pin "J12") (pinfunction "NC_J12") (pintype "passive"))
    )
    (net (code "143") (name "unconnected-(U2J-NC-PadJ13)") (class "Default")
      (node (ref "U2") (pin "J13") (pinfunction "NC_J13") (pintype "passive"))
    )
    (net (code "144") (name "unconnected-(U2J-NC-PadJ16)") (class "Default")
      (node (ref "U2") (pin "J16") (pinfunction "NC_J16") (pintype "passive"))
    )
    (net (code "145") (name "unconnected-(U2J-NC-PadK12)") (class "Default")
      (node (ref "U2") (pin "K12") (pinfunction "NC_K12") (pintype "passive"))
    )
    (net (code "146") (name "unconnected-(U2J-NC-PadK14)") (class "Default")
      (node (ref "U2") (pin "K14") (pinfunction "NC_K14") (pintype "passive"))
    )
    (net (code "147") (name "unconnected-(U2J-NC-PadK15)") (class "Default")
      (node (ref "U2") (pin "K15") (pinfunction "NC_K15") (pintype "passive"))
    )
  )
)
